# Esquematico.net
KiCad netlist of a schematic drawn in EAGLE
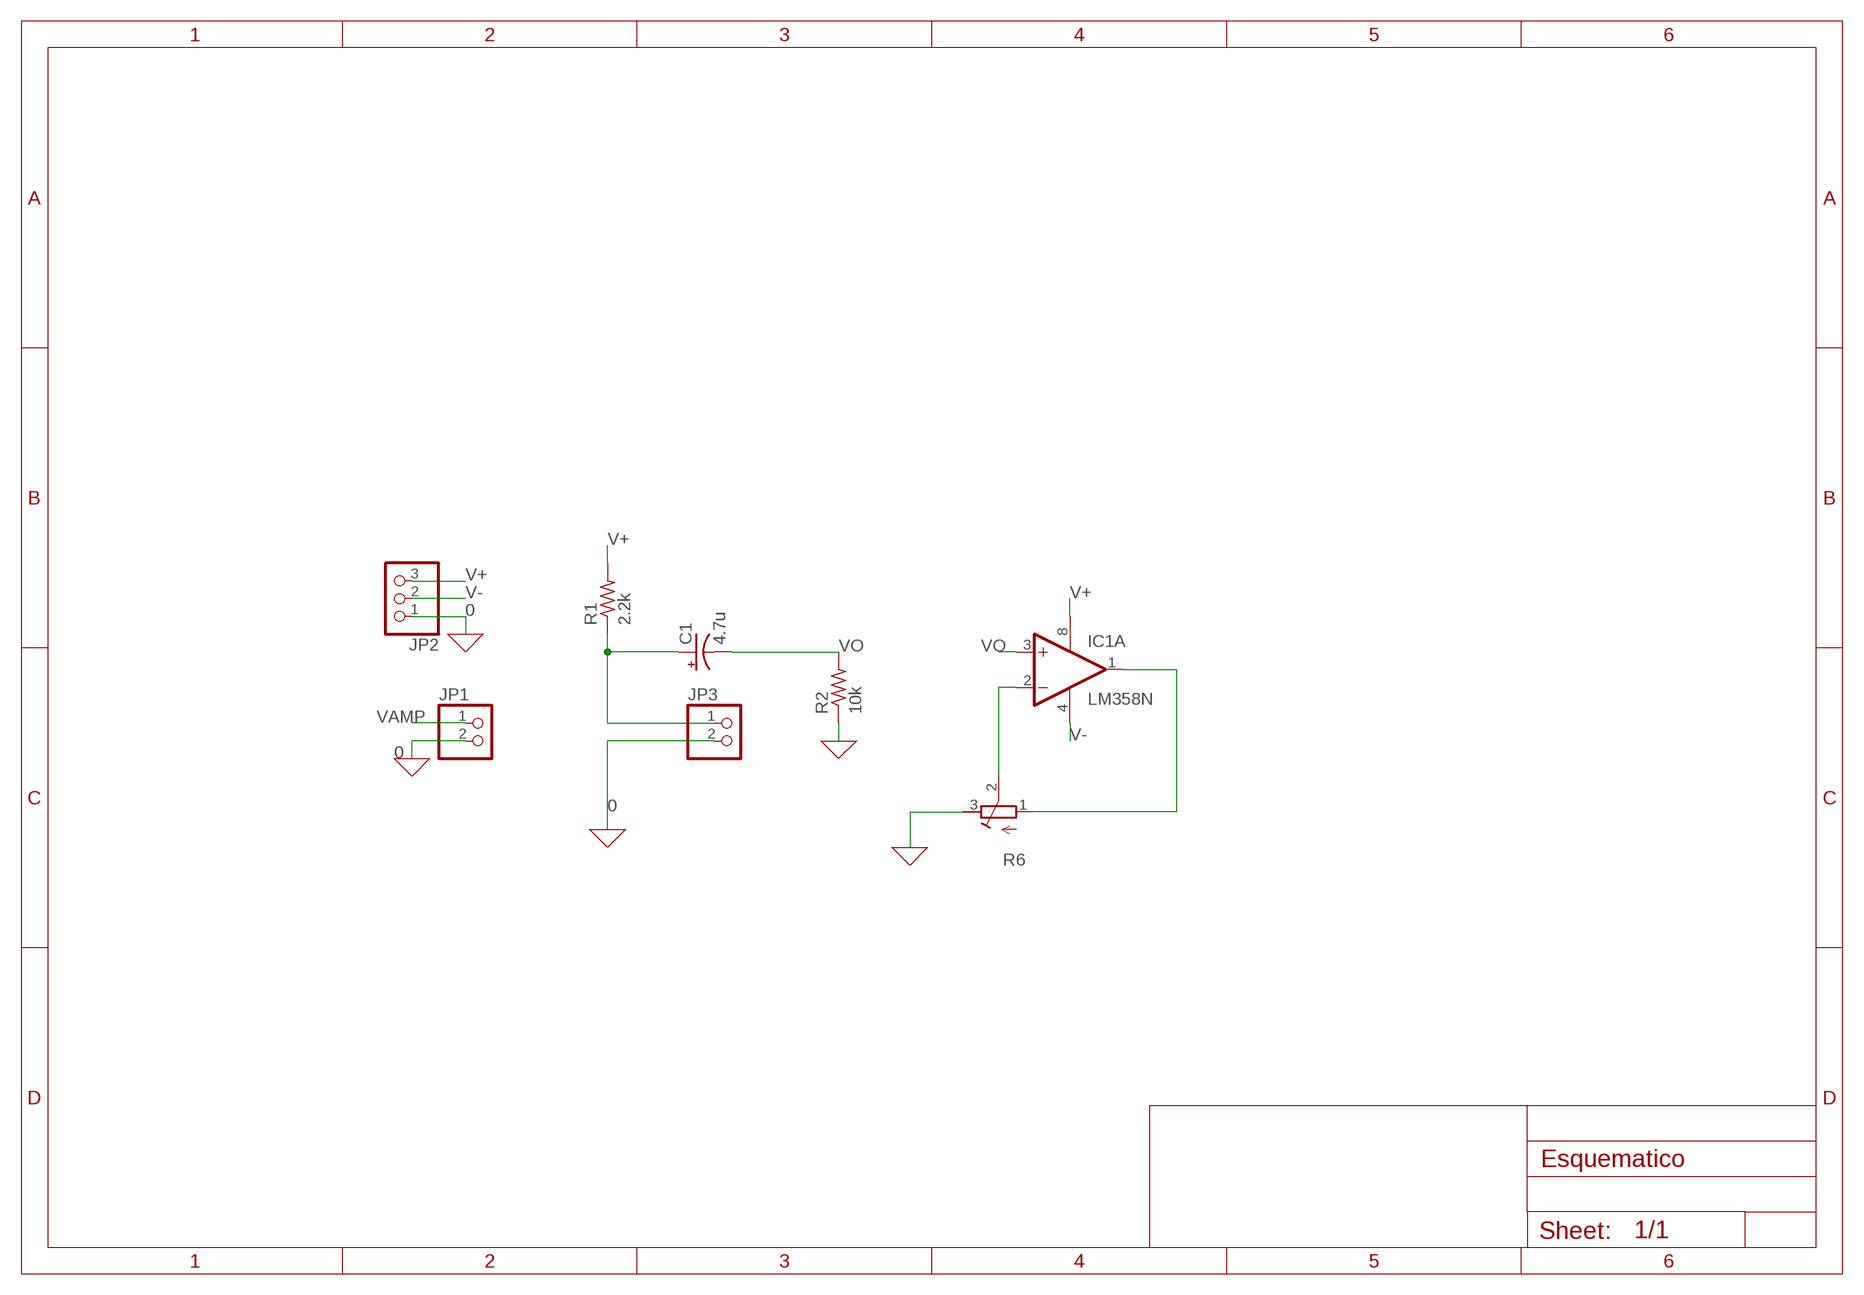
[diagram p0: schematic, sheet 1]

(export (version "E")
  (design (tool "Eeschema 10.0.6"))
  (components
    (comp (ref "C1")
      (value "4.7u")
      (footprint "eagle-import:E3,5-8")
      (libsource (lib "eagle-import") (part "CPOL-USE3.5-8"))
    )
    (comp (ref "IC1")
      (value "LM358N")
      (footprint "eagle-import:DIL08")
      (libsource (lib "eagle-import") (part "LM358N"))
    )
    (comp (ref "JP1")
      (value "PINHD-1X2")
      (footprint "eagle-import:1X02")
      (libsource (lib "eagle-import") (part "PINHD-1X2"))
    )
    (comp (ref "JP2")
      (value "PINHD-1X3")
      (footprint "eagle-import:1X03")
      (libsource (lib "eagle-import") (part "PINHD-1X3"))
    )
    (comp (ref "JP3")
      (value "PINHD-1X2")
      (footprint "eagle-import:1X02")
      (libsource (lib "eagle-import") (part "PINHD-1X2"))
    )
    (comp (ref "R1")
      (value "2.2k")
      (footprint "eagle-import:0207_10")
      (libsource (lib "eagle-import") (part "R-US_0207/10"))
    )
    (comp (ref "R2")
      (value "10k")
      (footprint "eagle-import:0207_10")
      (libsource (lib "eagle-import") (part "R-US_0207/10"))
    )
    (comp (ref "R6")
      (value "R-TRIMM64W")
      (footprint "eagle-import:RTRIM64W")
      (libsource (lib "eagle-import") (part "R-TRIMM64W"))
    )
  )
  (nets
    (net (code "1") (name "/V+") (class "Default")
      (node (ref "IC1") (pin "8") (pinfunction "V+_8") (pintype "power_in"))
      (node (ref "JP2") (pin "3") (pinfunction "3_3") (pintype "passive"))
      (node (ref "R1") (pin "2") (pinfunction "2_2") (pintype "passive"))
    )
    (net (code "2") (name "/V-") (class "Default")
      (node (ref "IC1") (pin "4") (pinfunction "V-_4") (pintype "power_in"))
      (node (ref "JP2") (pin "2") (pinfunction "2_2") (pintype "passive"))
    )
    (net (code "3") (name "/VAMP") (class "Default")
      (node (ref "IC1") (pin "1") (pinfunction "OUT_1") (pintype "output"))
      (node (ref "JP1") (pin "1") (pinfunction "1_1") (pintype "passive"))
      (node (ref "R6") (pin "1") (pinfunction "A_1") (pintype "passive"))
    )
    (net (code "4") (name "/VO") (class "Default")
      (node (ref "C1") (pin "-") (pinfunction "-_-") (pintype "passive"))
      (node (ref "IC1") (pin "3") (pinfunction "+IN_3") (pintype "input"))
      (node (ref "R2") (pin "2") (pinfunction "2_2") (pintype "passive"))
    )
    (net (code "5") (name "GND") (class "Default")
      (node (ref "JP1") (pin "2") (pinfunction "2_2") (pintype "passive"))
      (node (ref "JP2") (pin "1") (pinfunction "1_1") (pintype "passive"))
      (node (ref "JP3") (pin "2") (pinfunction "2_2") (pintype "passive"))
      (node (ref "R2") (pin "1") (pinfunction "1_1") (pintype "passive"))
      (node (ref "R6") (pin "3") (pinfunction "E_3") (pintype "passive"))
    )
    (net (code "6") (name "Net-(C1-Pad+)") (class "Default")
      (node (ref "C1") (pin "+") (pinfunction "+_+") (pintype "passive"))
      (node (ref "JP3") (pin "1") (pinfunction "1_1") (pintype "passive"))
      (node (ref "R1") (pin "1") (pinfunction "1_1") (pintype "passive"))
    )
    (net (code "7") (name "Net-(IC1A--IN)") (class "Default")
      (node (ref "IC1") (pin "2") (pinfunction "-IN_2") (pintype "input"))
      (node (ref "R6") (pin "2") (pinfunction "S_2") (pintype "passive"))
    )
  )
)
